# FLXWTCH_OLED.net
KiCad netlist of a schematic drawn in EAGLE
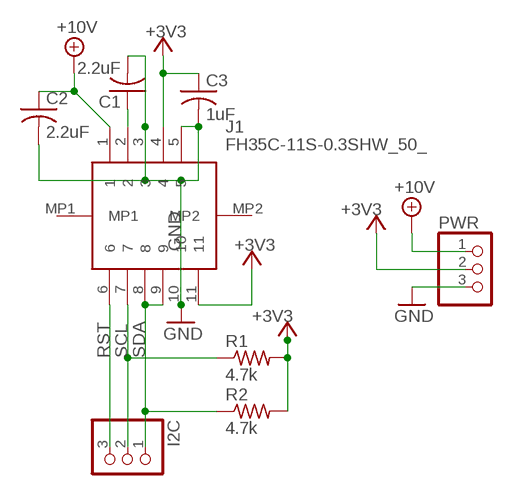
[diagram p0: schematic, sheet 1]

(export (version "E")
  (design (tool "Eeschema 10.0.6"))
  (components
    (comp (ref "C1")
      (value "2.2uF")
      (footprint "eagle-import:C0603K")
      (libsource (lib "eagle-import") (part "C-USC0603K"))
    )
    (comp (ref "C2")
      (value "2.2uF")
      (footprint "eagle-import:C0603K")
      (libsource (lib "eagle-import") (part "C-USC0603K"))
    )
    (comp (ref "C3")
      (value "1uF")
      (footprint "eagle-import:C0603K")
      (libsource (lib "eagle-import") (part "C-USC0603K"))
    )
    (comp (ref "I2C")
      (value "PINHD-1X3")
      (footprint "eagle-import:1X03")
      (libsource (lib "eagle-import") (part "PINHD-1X3"))
    )
    (comp (ref "J1")
      (value "FH35C-11S-0.3SHW_50_")
      (footprint "eagle-import:FH35C11S03SHW50")
      (fields
        (field (name "MANUFACTURER_PART_NUMBER") "FH35C-11S-0.3SHW(50)")
        (field (name "MOUSER_PART_NUMBER") "798-FH35C11S03SHW50")
      )
      (libsource (lib "eagle-import") (part "FH35C-11S-0.3SHW_50_"))
    )
    (comp (ref "PWR")
      (value "PINHD-1X3")
      (footprint "eagle-import:1X03")
      (libsource (lib "eagle-import") (part "PINHD-1X3"))
    )
    (comp (ref "R1")
      (value "4.7k")
      (footprint "eagle-import:R0603")
      (libsource (lib "eagle-import") (part "R-US_R0603"))
    )
    (comp (ref "R2")
      (value "4.7k")
      (footprint "eagle-import:R0603")
      (libsource (lib "eagle-import") (part "R-US_R0603"))
    )
  )
  (nets
    (net (code "1") (name "+3V3") (class "Default")
      (node (ref "C3") (pin "1") (pinfunction "1_1") (pintype "passive"))
      (node (ref "J1") (pin "11") (pinfunction "11_11") (pintype "bidirectional"))
      (node (ref "J1") (pin "4") (pinfunction "4_4") (pintype "bidirectional"))
      (node (ref "PWR") (pin "2") (pinfunction "2_2") (pintype "passive"))
      (node (ref "R1") (pin "2") (pinfunction "2_2") (pintype "passive"))
      (node (ref "R2") (pin "2") (pinfunction "2_2") (pintype "passive"))
    )
    (net (code "2") (name "+10V") (class "Default")
      (node (ref "C2") (pin "1") (pinfunction "1_1") (pintype "passive"))
      (node (ref "J1") (pin "1") (pinfunction "1_1") (pintype "bidirectional"))
      (node (ref "PWR") (pin "1") (pinfunction "1_1") (pintype "passive"))
    )
    (net (code "3") (name "/RST") (class "Default")
      (node (ref "I2C") (pin "3") (pinfunction "3_3") (pintype "passive"))
      (node (ref "J1") (pin "6") (pinfunction "6_6") (pintype "bidirectional"))
    )
    (net (code "4") (name "/SCL") (class "Default")
      (node (ref "I2C") (pin "2") (pinfunction "2_2") (pintype "passive"))
      (node (ref "J1") (pin "7") (pinfunction "7_7") (pintype "bidirectional"))
      (node (ref "R1") (pin "1") (pinfunction "1_1") (pintype "passive"))
    )
    (net (code "5") (name "/SDA") (class "Default")
      (node (ref "I2C") (pin "1") (pinfunction "1_1") (pintype "passive"))
      (node (ref "J1") (pin "8") (pinfunction "8_8") (pintype "bidirectional"))
      (node (ref "J1") (pin "9") (pinfunction "9_9") (pintype "bidirectional"))
      (node (ref "R2") (pin "1") (pinfunction "1_1") (pintype "passive"))
    )
    (net (code "6") (name "GND") (class "Default")
      (node (ref "C1") (pin "2") (pinfunction "2_2") (pintype "passive"))
      (node (ref "C2") (pin "2") (pinfunction "2_2") (pintype "passive"))
      (node (ref "C3") (pin "2") (pinfunction "2_2") (pintype "passive"))
      (node (ref "J1") (pin "10") (pinfunction "10_10") (pintype "bidirectional"))
      (node (ref "J1") (pin "3") (pinfunction "3_3") (pintype "bidirectional"))
      (node (ref "J1") (pin "5") (pinfunction "5_5") (pintype "bidirectional"))
      (node (ref "PWR") (pin "3") (pinfunction "3_3") (pintype "passive"))
    )
    (net (code "7") (name "Net-(C1-Pad1)") (class "Default")
      (node (ref "C1") (pin "1") (pinfunction "1_1") (pintype "passive"))
      (node (ref "J1") (pin "2") (pinfunction "2_2") (pintype "bidirectional"))
    )
    (net (code "8") (name "unconnected-(J1-PadMP1)") (class "Default")
      (node (ref "J1") (pin "MP1") (pinfunction "MP1_MP1") (pintype "bidirectional"))
    )
    (net (code "9") (name "unconnected-(J1-PadMP2)") (class "Default")
      (node (ref "J1") (pin "MP2") (pinfunction "MP2_MP2") (pintype "bidirectional"))
    )
  )
)
